# Power_Control.net
KiCad netlist of a schematic drawn in EasyEDA Pro
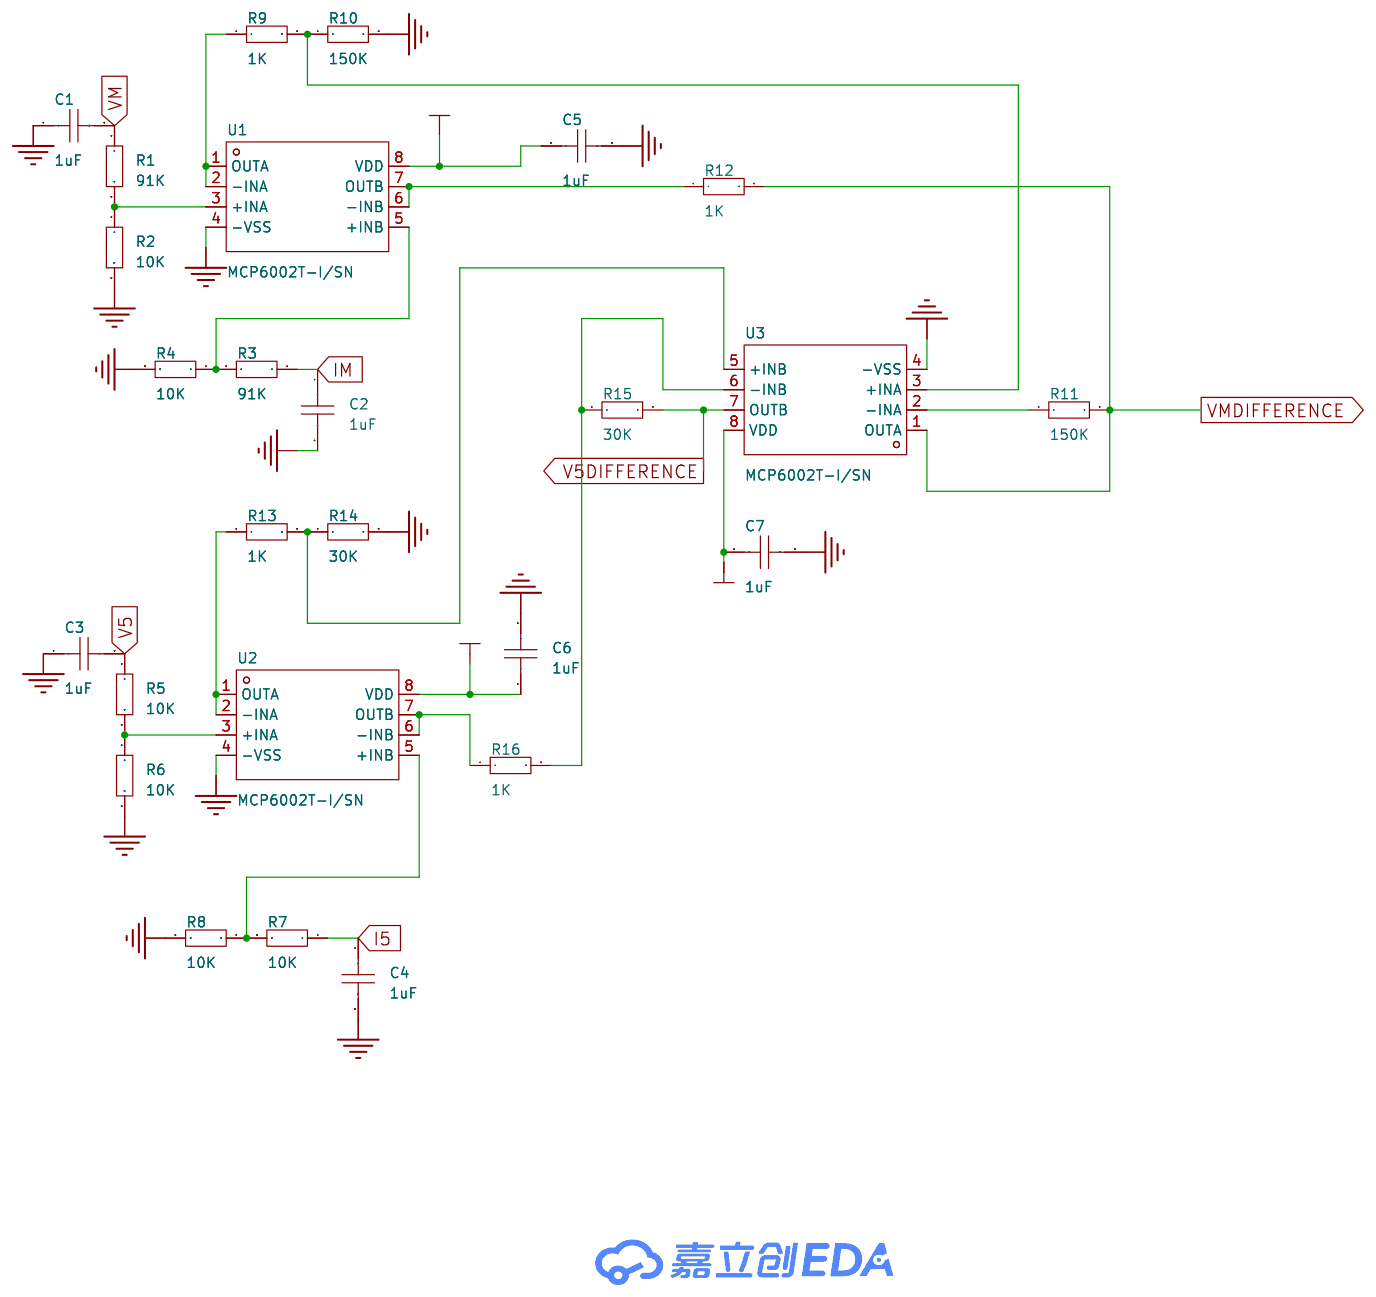
[diagram p0: schematic sheet]

(export (version "E")
  (design (tool "Eeschema 10.0.6"))
  (components
    (comp (ref "C1")
      (value "1uF")
      (footprint "easyedapro:C0603")
      (libsource (lib "easyedapro") (part "CapAcitance"))
    )
    (comp (ref "C2")
      (value "1uF")
      (footprint "easyedapro:C0603")
      (libsource (lib "easyedapro") (part "CapAcitance"))
    )
    (comp (ref "C3")
      (value "1uF")
      (footprint "easyedapro:C0603")
      (libsource (lib "easyedapro") (part "CapAcitance"))
    )
    (comp (ref "C4")
      (value "1uF")
      (footprint "easyedapro:C0603")
      (libsource (lib "easyedapro") (part "CapAcitance"))
    )
    (comp (ref "C5")
      (value "1uF")
      (footprint "easyedapro:C0603")
      (libsource (lib "easyedapro") (part "CapAcitance"))
    )
    (comp (ref "C6")
      (value "1uF")
      (footprint "easyedapro:C0603")
      (libsource (lib "easyedapro") (part "CapAcitance"))
    )
    (comp (ref "C7")
      (value "1uF")
      (footprint "easyedapro:C0603")
      (libsource (lib "easyedapro") (part "CapAcitance"))
    )
    (comp (ref "R1") (value "91K") (footprint "easyedapro:R0603") (libsource (lib "easyedapro") (part "电阻")))
    (comp (ref "R2") (value "10K") (footprint "easyedapro:R0603") (libsource (lib "easyedapro") (part "电阻")))
    (comp (ref "R3") (value "91K") (footprint "easyedapro:R0603") (libsource (lib "easyedapro") (part "电阻")))
    (comp (ref "R4") (value "10K") (footprint "easyedapro:R0603") (libsource (lib "easyedapro") (part "电阻")))
    (comp (ref "R5") (value "10K") (footprint "easyedapro:R0603") (libsource (lib "easyedapro") (part "电阻")))
    (comp (ref "R6") (value "10K") (footprint "easyedapro:R0603") (libsource (lib "easyedapro") (part "电阻")))
    (comp (ref "R7") (value "10K") (footprint "easyedapro:R0603") (libsource (lib "easyedapro") (part "电阻")))
    (comp (ref "R8") (value "10K") (footprint "easyedapro:R0603") (libsource (lib "easyedapro") (part "电阻")))
    (comp (ref "R9") (value "1K") (footprint "easyedapro:R0603") (libsource (lib "easyedapro") (part "电阻")))
    (comp (ref "R10")
      (value "150K")
      (footprint "easyedapro:R0603")
      (libsource (lib "easyedapro") (part "电阻"))
    )
    (comp (ref "R11")
      (value "150K")
      (footprint "easyedapro:R0603")
      (libsource (lib "easyedapro") (part "电阻"))
    )
    (comp (ref "R12") (value "1K") (footprint "easyedapro:R0603") (libsource (lib "easyedapro") (part "电阻")))
    (comp (ref "R13") (value "1K") (footprint "easyedapro:R0603") (libsource (lib "easyedapro") (part "电阻")))
    (comp (ref "R14") (value "30K") (footprint "easyedapro:R0603") (libsource (lib "easyedapro") (part "电阻")))
    (comp (ref "R15") (value "30K") (footprint "easyedapro:R0603") (libsource (lib "easyedapro") (part "电阻")))
    (comp (ref "R16") (value "1K") (footprint "easyedapro:R0603") (libsource (lib "easyedapro") (part "电阻")))
    (comp (ref "U1")
      (value "MCP6002T-I/SN")
      (footprint "easyedapro:SOIC-8_L4.9-W3.9-P1.27-LS6.0-BL")
      (description "放大器数:双路;轨到轨:-;增益带宽积(GBP):-;输入失调电压(Vos):4.5mV;压摆率(SR):600V/ms;输入偏置电流(Ib):1pA;")
      (fields (field (name "Manufacturer") "MICROCHIP(美国微芯)"))
      (libsource (lib "easyedapro") (part "MCP6002T-I/SN"))
    )
    (comp (ref "U2")
      (value "MCP6002T-I/SN")
      (footprint "easyedapro:SOIC-8_L4.9-W3.9-P1.27-LS6.0-BL")
      (description "放大器数:双路;轨到轨:-;增益带宽积(GBP):-;输入失调电压(Vos):4.5mV;压摆率(SR):600V/ms;输入偏置电流(Ib):1pA;")
      (fields (field (name "Manufacturer") "MICROCHIP(美国微芯)"))
      (libsource (lib "easyedapro") (part "MCP6002T-I/SN"))
    )
    (comp (ref "U3")
      (value "MCP6002T-I/SN")
      (footprint "easyedapro:SOIC-8_L4.9-W3.9-P1.27-LS6.0-BL")
      (description "放大器数:双路;轨到轨:-;增益带宽积(GBP):-;输入失调电压(Vos):4.5mV;压摆率(SR):600V/ms;输入偏置电流(Ib):1pA;")
      (fields (field (name "Manufacturer") "MICROCHIP(美国微芯)"))
      (libsource (lib "easyedapro") (part "MCP6002T-I/SN"))
    )
  )
  (nets
    (net (code "1") (name "+3.3V") (class "Default")
      (node (ref "C5") (pin "1") (pinfunction "1_1") (pintype "input"))
      (node (ref "C6") (pin "1") (pinfunction "1_1") (pintype "input"))
      (node (ref "U1") (pin "8") (pinfunction "VDD_8") (pintype "unspecified"))
      (node (ref "U2") (pin "8") (pinfunction "VDD_8") (pintype "unspecified"))
    )
    (net (code "2") (name "3.3V") (class "Default")
      (node (ref "C7") (pin "1") (pinfunction "1_1") (pintype "input"))
      (node (ref "U3") (pin "8") (pinfunction "VDD_8") (pintype "unspecified"))
    )
    (net (code "3") (name "GND") (class "Default")
      (node (ref "C1") (pin "1") (pinfunction "1_1") (pintype "input"))
      (node (ref "C2") (pin "2") (pinfunction "2_2") (pintype "input"))
      (node (ref "C3") (pin "1") (pinfunction "1_1") (pintype "input"))
      (node (ref "C5") (pin "2") (pinfunction "2_2") (pintype "input"))
      (node (ref "C6") (pin "2") (pinfunction "2_2") (pintype "input"))
      (node (ref "C7") (pin "2") (pinfunction "2_2") (pintype "input"))
      (node (ref "R10") (pin "2") (pinfunction "2_2") (pintype "input"))
      (node (ref "R14") (pin "2") (pinfunction "2_2") (pintype "input"))
      (node (ref "R2") (pin "2") (pinfunction "2_2") (pintype "input"))
      (node (ref "R4") (pin "2") (pinfunction "2_2") (pintype "input"))
      (node (ref "R6") (pin "2") (pinfunction "2_2") (pintype "input"))
      (node (ref "R8") (pin "2") (pinfunction "2_2") (pintype "input"))
      (node (ref "U1") (pin "4") (pinfunction "-VSS_4") (pintype "unspecified"))
      (node (ref "U2") (pin "4") (pinfunction "-VSS_4") (pintype "unspecified"))
      (node (ref "U3") (pin "4") (pinfunction "-VSS_4") (pintype "unspecified"))
    )
    (net (code "4") (name "I5") (class "Default")
      (node (ref "C4") (pin "1") (pinfunction "1_1") (pintype "input"))
      (node (ref "C4") (pin "2") (pinfunction "2_2") (pintype "input"))
      (node (ref "R7") (pin "1") (pinfunction "1_1") (pintype "input"))
    )
    (net (code "5") (name "IM") (class "Default")
      (node (ref "C2") (pin "1") (pinfunction "1_1") (pintype "input"))
      (node (ref "R3") (pin "1") (pinfunction "1_1") (pintype "input"))
    )
    (net (code "6") (name "Net-(U1-+INA)") (class "Default")
      (node (ref "R1") (pin "2") (pinfunction "2_2") (pintype "input"))
      (node (ref "R2") (pin "1") (pinfunction "1_1") (pintype "input"))
      (node (ref "U1") (pin "3") (pinfunction "+INA_3") (pintype "unspecified"))
    )
    (net (code "7") (name "Net-(U1-+INB)") (class "Default")
      (node (ref "R3") (pin "2") (pinfunction "2_2") (pintype "input"))
      (node (ref "R4") (pin "1") (pinfunction "1_1") (pintype "input"))
      (node (ref "U1") (pin "5") (pinfunction "+INB_5") (pintype "unspecified"))
    )
    (net (code "8") (name "Net-(U1--INA)") (class "Default")
      (node (ref "R9") (pin "1") (pinfunction "1_1") (pintype "input"))
      (node (ref "U1") (pin "1") (pinfunction "OUTA_1") (pintype "unspecified"))
      (node (ref "U1") (pin "2") (pinfunction "-INA_2") (pintype "unspecified"))
    )
    (net (code "9") (name "Net-(U1--INB)") (class "Default")
      (node (ref "R12") (pin "1") (pinfunction "1_1") (pintype "input"))
      (node (ref "U1") (pin "6") (pinfunction "-INB_6") (pintype "unspecified"))
      (node (ref "U1") (pin "7") (pinfunction "OUTB_7") (pintype "unspecified"))
    )
    (net (code "10") (name "Net-(U2-+INA)") (class "Default")
      (node (ref "R5") (pin "2") (pinfunction "2_2") (pintype "input"))
      (node (ref "R6") (pin "1") (pinfunction "1_1") (pintype "input"))
      (node (ref "U2") (pin "3") (pinfunction "+INA_3") (pintype "unspecified"))
    )
    (net (code "11") (name "Net-(U2-+INB)") (class "Default")
      (node (ref "R7") (pin "2") (pinfunction "2_2") (pintype "input"))
      (node (ref "R8") (pin "1") (pinfunction "1_1") (pintype "input"))
      (node (ref "U2") (pin "5") (pinfunction "+INB_5") (pintype "unspecified"))
    )
    (net (code "12") (name "Net-(U2--INA)") (class "Default")
      (node (ref "R13") (pin "1") (pinfunction "1_1") (pintype "input"))
      (node (ref "U2") (pin "1") (pinfunction "OUTA_1") (pintype "unspecified"))
      (node (ref "U2") (pin "2") (pinfunction "-INA_2") (pintype "unspecified"))
    )
    (net (code "13") (name "Net-(U2--INB)") (class "Default")
      (node (ref "R16") (pin "1") (pinfunction "1_1") (pintype "input"))
      (node (ref "U2") (pin "6") (pinfunction "-INB_6") (pintype "unspecified"))
      (node (ref "U2") (pin "7") (pinfunction "OUTB_7") (pintype "unspecified"))
    )
    (net (code "14") (name "Net-(U3-+INA)") (class "Default")
      (node (ref "R10") (pin "1") (pinfunction "1_1") (pintype "input"))
      (node (ref "R9") (pin "2") (pinfunction "2_2") (pintype "input"))
      (node (ref "U3") (pin "3") (pinfunction "+INA_3") (pintype "unspecified"))
    )
    (net (code "15") (name "Net-(U3-+INB)") (class "Default")
      (node (ref "R13") (pin "2") (pinfunction "2_2") (pintype "input"))
      (node (ref "R14") (pin "1") (pinfunction "1_1") (pintype "input"))
      (node (ref "U3") (pin "5") (pinfunction "+INB_5") (pintype "unspecified"))
    )
    (net (code "16") (name "Net-(U3--INA)") (class "Default")
      (node (ref "R11") (pin "1") (pinfunction "1_1") (pintype "input"))
      (node (ref "U3") (pin "2") (pinfunction "-INA_2") (pintype "unspecified"))
    )
    (net (code "17") (name "Net-(U3--INB)") (class "Default")
      (node (ref "R15") (pin "1") (pinfunction "1_1") (pintype "input"))
      (node (ref "R16") (pin "2") (pinfunction "2_2") (pintype "input"))
      (node (ref "U3") (pin "6") (pinfunction "-INB_6") (pintype "unspecified"))
    )
    (net (code "18") (name "V5") (class "Default")
      (node (ref "C3") (pin "2") (pinfunction "2_2") (pintype "input"))
      (node (ref "R5") (pin "1") (pinfunction "1_1") (pintype "input"))
    )
    (net (code "19") (name "V5DIFFERENCE") (class "Default")
      (node (ref "R15") (pin "2") (pinfunction "2_2") (pintype "input"))
      (node (ref "U3") (pin "7") (pinfunction "OUTB_7") (pintype "unspecified"))
    )
    (net (code "20") (name "VM") (class "Default")
      (node (ref "C1") (pin "2") (pinfunction "2_2") (pintype "input"))
      (node (ref "R1") (pin "1") (pinfunction "1_1") (pintype "input"))
    )
    (net (code "21") (name "VMDIFFERENCE") (class "Default")
      (node (ref "R11") (pin "2") (pinfunction "2_2") (pintype "input"))
      (node (ref "R12") (pin "2") (pinfunction "2_2") (pintype "input"))
      (node (ref "U3") (pin "1") (pinfunction "OUTA_1") (pintype "unspecified"))
    )
  )
)
